# Connectors.net
KiCad netlist of a schematic drawn in Altium Designer
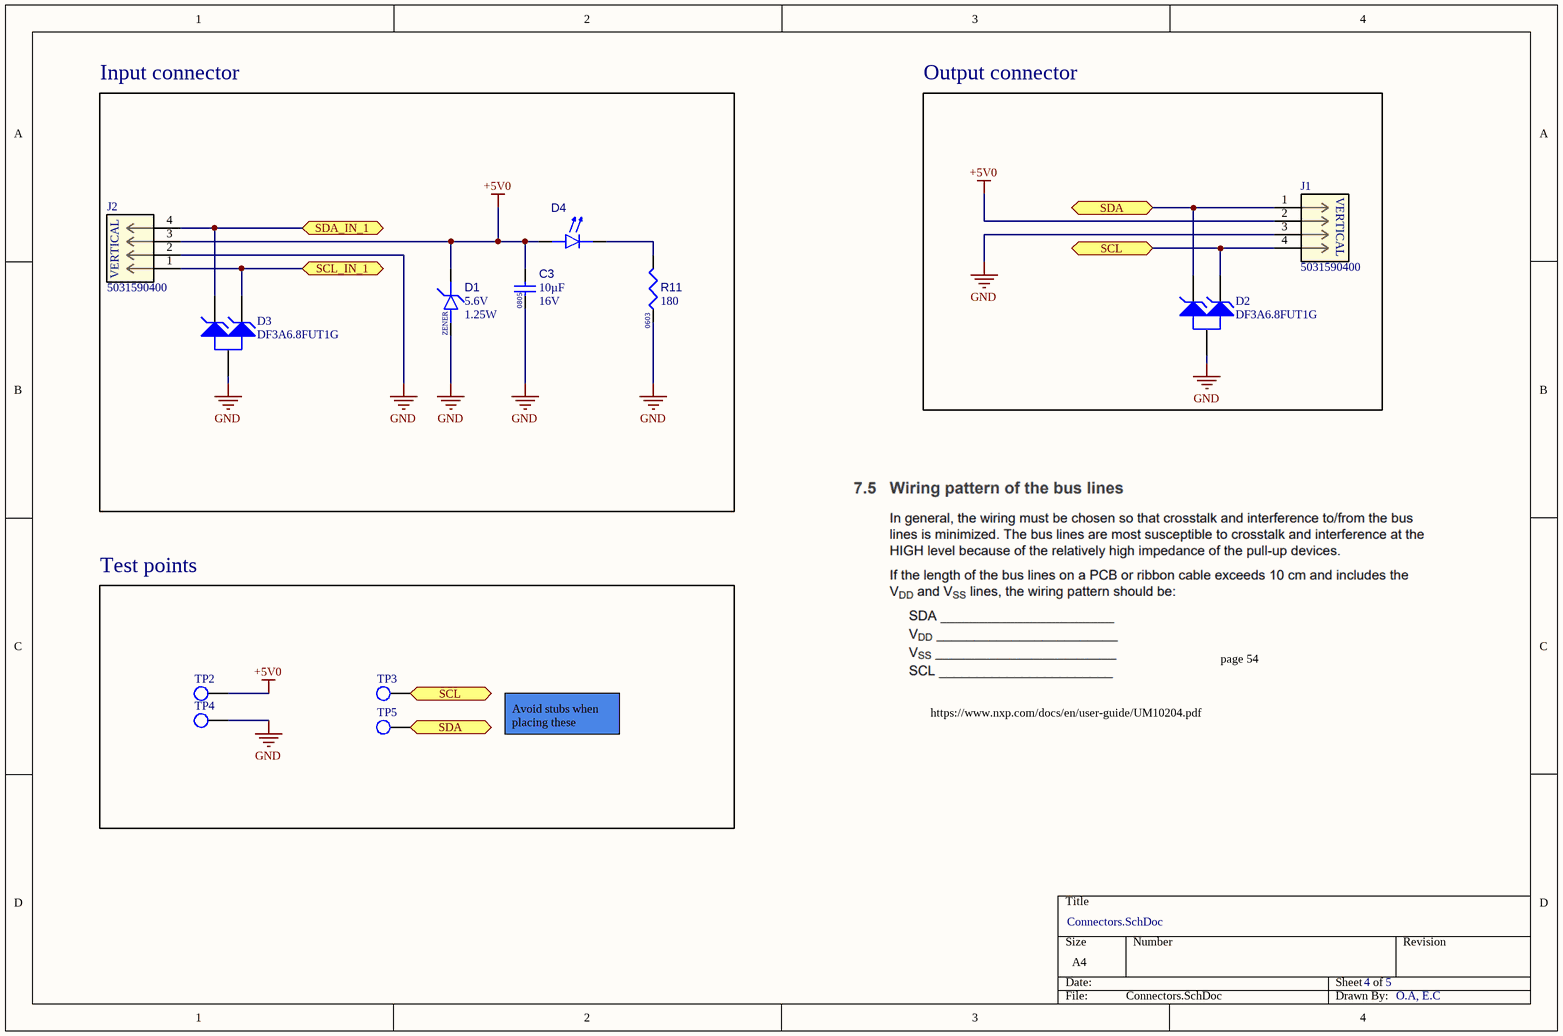
[diagram p0: Connectors.SchDoc]

(export (version "E")
  (design (tool "Eeschema 10.0.6"))
  (components
    (comp (ref "C3")
      (value "10µF")
      (footprint "CAP CER 10UF 16V X5R 0805-Footprint-1")
      (fields
        (field (name "VOLTAGE RATING") "16V")
        (field (name "CASE/PACKAGE") "0805")
        (field (name "Comment") "CAP CER 10UF 16V X5R 0805")
      )
      (libsource (lib "hawaiirobotics") (part "CAP-NP-2"))
    )
    (comp (ref "D1")
      (value "BZG05C5V6-M3-08")
      (footprint "FP-S8-V-3848_01-003-MFG")
      (description "Zener Diode, 5.6V V(Z), 7.14%, 1.25W, Silicon, Unidirectional, DO-214AC")
      (fields
        (field (name "DIODE TYPE") "ZENER")
        (field (name "REFERENCE VOLTAGE-NOM") "5.6V")
        (field (name "MAX POWER DISSIPATION") "1.25W")
      )
      (libsource (lib "hawaiirobotics") (part "DIODE-2"))
    )
    (comp (ref "D2")
      (value "DF3A6.8FUT1G")
      (footprint "ONSC-SC-70-3-419-04_V")
      (description "Trans Voltage Suppressor Diode, 150W, Unidirectional, 2 Element, Silicon")
      (libsource (lib "hawaiirobotics") (part "ONSC-K1K2A3-3"))
    )
    (comp (ref "D3")
      (value "DF3A6.8FUT1G")
      (footprint "ONSC-SC-70-3-419-04_V")
      (description "Trans Voltage Suppressor Diode, 150W, Unidirectional, 2 Element, Silicon")
      (libsource (lib "hawaiirobotics") (part "ONSC-K1K2A3-3"))
    )
    (comp (ref "D4")
      (value "150060RS75000")
      (footprint "WL-SMCW_0603_150060xx75000")
      (description "Single Color LED, Red, Water Clear, 1.1mm")
      (libsource (lib "hawaiirobotics") (part "DIODE-LED-2"))
    )
    (comp (ref "J1")
      (value "5031590400")
      (footprint "5031590400-Footprint-1")
      (libsource (lib "hawaiirobotics") (part "5031590400-Symbol-1"))
    )
    (comp (ref "J2")
      (value "5031590400")
      (footprint "5031590400-Footprint-1")
      (libsource (lib "") (part "5031590400-Symbol-1_1"))
    )
    (comp (ref "R11")
      (value "180")
      (footprint "RESC0603(1608)_N")
      (fields
        (field (name "TOLERANCE") "5%")
        (field (name "CASE/PACKAGE") "0603")
        (field (name "POWER") "100mW")
        (field (name "Comment") "RC0603JR-07180RL")
      )
      (libsource (lib "hawaiirobotics") (part "RES-2"))
    )
    (comp (ref "TP2")
      (value "RCUCTE")
      (footprint "FP-S2761-46R-MFG")
      (description "Test point")
      (libsource (lib "hawaiirobotics") (part "RCUCTE-Symbol-1"))
    )
    (comp (ref "TP3")
      (value "RCUCTE")
      (footprint "FP-S2761-46R-MFG")
      (description "Test point")
      (libsource (lib "hawaiirobotics") (part "RCUCTE-Symbol-1"))
    )
    (comp (ref "TP4")
      (value "RCUCTE")
      (footprint "FP-S2761-46R-MFG")
      (description "Test point")
      (libsource (lib "hawaiirobotics") (part "RCUCTE-Symbol-1"))
    )
    (comp (ref "TP5")
      (value "RCUCTE")
      (footprint "FP-S2761-46R-MFG")
      (description "Test point")
      (libsource (lib "hawaiirobotics") (part "RCUCTE-Symbol-1"))
    )
  )
  (nets
    (net (code "1") (name "+5V0") (class "Default")
      (node (ref "C3") (pin "2") (pinfunction "2_2") (pintype "passive"))
      (node (ref "D1") (pin "1") (pinfunction "K_1") (pintype "passive"))
      (node (ref "D4") (pin "2") (pinfunction "A_2") (pintype "passive"))
      (node (ref "J1") (pin "2") (pinfunction "2_2") (pintype "passive"))
      (node (ref "J2") (pin "3") (pinfunction "3_3") (pintype "passive"))
      (node (ref "TP2") (pin "1") (pinfunction "1_1") (pintype "passive"))
    )
    (net (code "2") (name "/SCL") (class "Default")
      (node (ref "D2") (pin "2") (pinfunction "K2_2") (pintype "passive"))
      (node (ref "J1") (pin "4") (pinfunction "4_4") (pintype "passive"))
      (node (ref "TP3") (pin "1") (pinfunction "1_1") (pintype "passive"))
    )
    (net (code "3") (name "/SCL_IN_1") (class "Default")
      (node (ref "D3") (pin "2") (pinfunction "K2_2") (pintype "passive"))
      (node (ref "J2") (pin "1") (pinfunction "1_1") (pintype "passive"))
    )
    (net (code "4") (name "/SDA") (class "Default")
      (node (ref "D2") (pin "1") (pinfunction "K1_1") (pintype "passive"))
      (node (ref "J1") (pin "1") (pinfunction "1_1") (pintype "passive"))
      (node (ref "TP5") (pin "1") (pinfunction "1_1") (pintype "passive"))
    )
    (net (code "5") (name "/SDA_IN_1") (class "Default")
      (node (ref "D3") (pin "1") (pinfunction "K1_1") (pintype "passive"))
      (node (ref "J2") (pin "4") (pinfunction "4_4") (pintype "passive"))
    )
    (net (code "6") (name "GND") (class "Default")
      (node (ref "C3") (pin "1") (pinfunction "1_1") (pintype "passive"))
      (node (ref "D1") (pin "2") (pinfunction "A_2") (pintype "passive"))
      (node (ref "D2") (pin "3") (pinfunction "A_3") (pintype "passive"))
      (node (ref "D3") (pin "3") (pinfunction "A_3") (pintype "passive"))
      (node (ref "J1") (pin "3") (pinfunction "3_3") (pintype "passive"))
      (node (ref "J2") (pin "2") (pinfunction "2_2") (pintype "passive"))
      (node (ref "R11") (pin "1") (pinfunction "1_1") (pintype "passive"))
      (node (ref "TP4") (pin "1") (pinfunction "1_1") (pintype "passive"))
    )
    (net (code "7") (name "Net-(D4-K)") (class "Default")
      (node (ref "D4") (pin "1") (pinfunction "K_1") (pintype "passive"))
      (node (ref "R11") (pin "2") (pinfunction "2_2") (pintype "passive"))
    )
  )
)
